# Pyr0-Piezo-FFC-Direct-Creality-X-Board_2.net
KiCad netlist of a schematic drawn in EAGLE
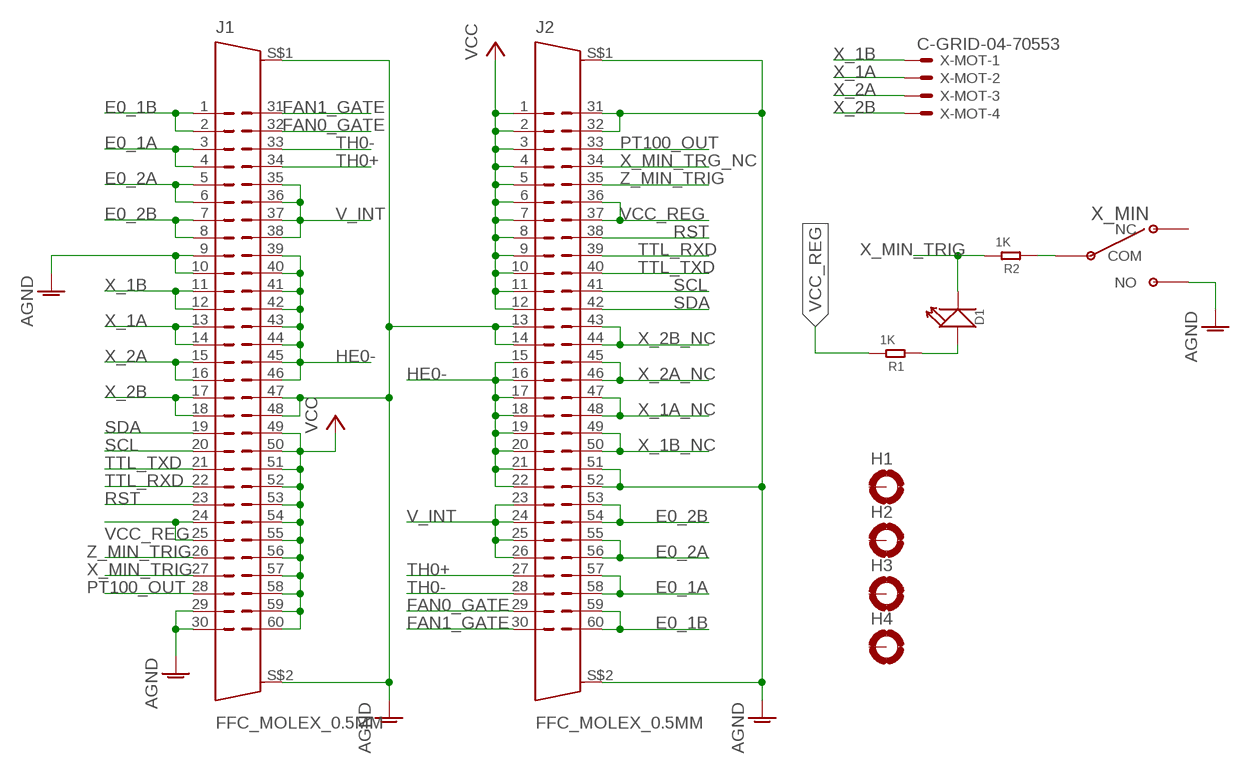
[diagram p0: schematic, sheet 1]

(export (version "E")
  (design (tool "Eeschema 10.0.6"))
  (components
    (comp (ref "D1")
      (value "SEEED-LED_SMD-LED-CLEAR-BLUE(0603)LED_0603")
      (footprint "eagle-import:SEEED-LED_LED-0603")
      (libsource (lib "eagle-import") (part "SEEED-LED_SMD-LED-CLEAR-BLUE(0603)LED_0603"))
    )
    (comp (ref "H1")
      (value "HOLES_MOUNT-PAD-ROUND3.2")
      (footprint "eagle-import:HOLES_3,2-PAD")
      (libsource (lib "eagle-import") (part "HOLES_MOUNT-PAD-ROUND3.2"))
    )
    (comp (ref "H2")
      (value "HOLES_MOUNT-PAD-ROUND3.2")
      (footprint "eagle-import:HOLES_3,2-PAD")
      (libsource (lib "eagle-import") (part "HOLES_MOUNT-PAD-ROUND3.2"))
    )
    (comp (ref "H3")
      (value "HOLES_MOUNT-PAD-ROUND3.2")
      (footprint "eagle-import:HOLES_3,2-PAD")
      (libsource (lib "eagle-import") (part "HOLES_MOUNT-PAD-ROUND3.2"))
    )
    (comp (ref "H4")
      (value "HOLES_MOUNT-PAD-ROUND3.2")
      (footprint "eagle-import:HOLES_3,2-PAD")
      (libsource (lib "eagle-import") (part "HOLES_MOUNT-PAD-ROUND3.2"))
    )
    (comp (ref "J1")
      (value "FFC_MOLEX_0.5MM")
      (footprint "eagle-import:FFC-60P_0.5_MOLEX_505110-6091")
      (libsource (lib "eagle-import") (part "FFC_MOLEX_0.5MM"))
    )
    (comp (ref "J2")
      (value "FFC_MOLEX_0.5MM")
      (footprint "eagle-import:FFC-60P_0.5_MOLEX_505110-6091")
      (libsource (lib "eagle-import") (part "FFC_MOLEX_0.5MM"))
    )
    (comp (ref "R1")
      (value "1K")
      (footprint "eagle-import:R0805")
      (fields (field (name "MPN") "RC0805JR-072KL"))
      (libsource (lib "eagle-import") (part "SMD-RES-2K-5%-1/8W(0805)"))
    )
    (comp (ref "R2")
      (value "1K")
      (footprint "eagle-import:R0805")
      (fields (field (name "MPN") "RC0805JR-072KL"))
      (libsource (lib "eagle-import") (part "SMD-RES-2K-5%-1/8W(0805)"))
    )
    (comp (ref "X-MOT")
      (value "C-GRID-04-70553")
      (footprint "eagle-import:70553-04")
      (fields (field (name "MF") "MOLEX"))
      (libsource (lib "eagle-import") (part "C-GRID-04-70553"))
    )
    (comp (ref "X_MIN")
      (value "LIMIT_SWITCHMICRO_SPDT_5.08")
      (footprint "eagle-import:MICROSWITCH_5.08")
      (libsource (lib "eagle-import") (part "LIMIT_SWITCHMICRO_SPDT_5.08"))
    )
  )
  (nets
    (net (code "1") (name "/E0_1A") (class "Default")
      (node (ref "J1") (pin "3") (pinfunction "5_3") (pintype "passive"))
      (node (ref "J1") (pin "4") (pinfunction "6_4") (pintype "passive"))
      (node (ref "J2") (pin "57") (pinfunction "63_57") (pintype "passive"))
      (node (ref "J2") (pin "58") (pinfunction "64_58") (pintype "passive"))
    )
    (net (code "2") (name "/E0_1B") (class "Default")
      (node (ref "J1") (pin "1") (pinfunction "3_1") (pintype "passive"))
      (node (ref "J1") (pin "2") (pinfunction "4_2") (pintype "passive"))
      (node (ref "J2") (pin "59") (pinfunction "65_59") (pintype "passive"))
      (node (ref "J2") (pin "60") (pinfunction "66_60") (pintype "passive"))
    )
    (net (code "3") (name "/E0_2A") (class "Default")
      (node (ref "J1") (pin "5") (pinfunction "7_5") (pintype "passive"))
      (node (ref "J1") (pin "6") (pinfunction "8_6") (pintype "passive"))
      (node (ref "J2") (pin "55") (pinfunction "61_55") (pintype "passive"))
      (node (ref "J2") (pin "56") (pinfunction "62_56") (pintype "passive"))
    )
    (net (code "4") (name "/E0_2B") (class "Default")
      (node (ref "J1") (pin "7") (pinfunction "9_7") (pintype "passive"))
      (node (ref "J1") (pin "8") (pinfunction "10_8") (pintype "passive"))
      (node (ref "J2") (pin "53") (pinfunction "59_53") (pintype "passive"))
      (node (ref "J2") (pin "54") (pinfunction "60_54") (pintype "passive"))
    )
    (net (code "5") (name "/FAN0_GATE") (class "Default")
      (node (ref "J1") (pin "32") (pinfunction "38_32") (pintype "passive"))
      (node (ref "J2") (pin "29") (pinfunction "31_29") (pintype "passive"))
    )
    (net (code "6") (name "/FAN1_GATE") (class "Default")
      (node (ref "J1") (pin "31") (pinfunction "37_31") (pintype "passive"))
      (node (ref "J2") (pin "30") (pinfunction "32_30") (pintype "passive"))
    )
    (net (code "7") (name "/HE0-") (class "Default")
      (node (ref "J1") (pin "39") (pinfunction "45_39") (pintype "passive"))
      (node (ref "J1") (pin "40") (pinfunction "46_40") (pintype "passive"))
      (node (ref "J1") (pin "41") (pinfunction "47_41") (pintype "passive"))
      (node (ref "J1") (pin "42") (pinfunction "48_42") (pintype "passive"))
      (node (ref "J1") (pin "43") (pinfunction "49_43") (pintype "passive"))
      (node (ref "J1") (pin "44") (pinfunction "50_44") (pintype "passive"))
      (node (ref "J1") (pin "45") (pinfunction "51_45") (pintype "passive"))
      (node (ref "J1") (pin "46") (pinfunction "52_46") (pintype "passive"))
      (node (ref "J2") (pin "15") (pinfunction "17_15") (pintype "passive"))
      (node (ref "J2") (pin "16") (pinfunction "18_16") (pintype "passive"))
      (node (ref "J2") (pin "17") (pinfunction "19_17") (pintype "passive"))
      (node (ref "J2") (pin "18") (pinfunction "20_18") (pintype "passive"))
      (node (ref "J2") (pin "19") (pinfunction "21_19") (pintype "passive"))
      (node (ref "J2") (pin "20") (pinfunction "22_20") (pintype "passive"))
      (node (ref "J2") (pin "21") (pinfunction "23_21") (pintype "passive"))
      (node (ref "J2") (pin "22") (pinfunction "24_22") (pintype "passive"))
    )
    (net (code "8") (name "/PT100_OUT") (class "Default")
      (node (ref "J1") (pin "28") (pinfunction "30_28") (pintype "passive"))
      (node (ref "J2") (pin "33") (pinfunction "39_33") (pintype "passive"))
    )
    (net (code "9") (name "/RST") (class "Default")
      (node (ref "J1") (pin "23") (pinfunction "25_23") (pintype "passive"))
      (node (ref "J2") (pin "38") (pinfunction "44_38") (pintype "passive"))
    )
    (net (code "10") (name "/SCL") (class "Default")
      (node (ref "J1") (pin "20") (pinfunction "22_20") (pintype "passive"))
      (node (ref "J2") (pin "41") (pinfunction "47_41") (pintype "passive"))
    )
    (net (code "11") (name "/SDA") (class "Default")
      (node (ref "J1") (pin "19") (pinfunction "21_19") (pintype "passive"))
      (node (ref "J2") (pin "42") (pinfunction "48_42") (pintype "passive"))
    )
    (net (code "12") (name "/TH0+") (class "Default")
      (node (ref "J1") (pin "34") (pinfunction "40_34") (pintype "passive"))
      (node (ref "J2") (pin "27") (pinfunction "29_27") (pintype "passive"))
    )
    (net (code "13") (name "/TH0-") (class "Default")
      (node (ref "J1") (pin "33") (pinfunction "39_33") (pintype "passive"))
      (node (ref "J2") (pin "28") (pinfunction "30_28") (pintype "passive"))
    )
    (net (code "14") (name "/TTL_RXD") (class "Default")
      (node (ref "J1") (pin "22") (pinfunction "24_22") (pintype "passive"))
      (node (ref "J2") (pin "39") (pinfunction "45_39") (pintype "passive"))
    )
    (net (code "15") (name "/TTL_TXD") (class "Default")
      (node (ref "J1") (pin "21") (pinfunction "23_21") (pintype "passive"))
      (node (ref "J2") (pin "40") (pinfunction "46_40") (pintype "passive"))
    )
    (net (code "16") (name "/V_INT") (class "Default")
      (node (ref "J1") (pin "35") (pinfunction "41_35") (pintype "passive"))
      (node (ref "J1") (pin "36") (pinfunction "42_36") (pintype "passive"))
      (node (ref "J1") (pin "37") (pinfunction "43_37") (pintype "passive"))
      (node (ref "J1") (pin "38") (pinfunction "44_38") (pintype "passive"))
      (node (ref "J2") (pin "23") (pinfunction "25_23") (pintype "passive"))
      (node (ref "J2") (pin "24") (pinfunction "26_24") (pintype "passive"))
      (node (ref "J2") (pin "25") (pinfunction "27_25") (pintype "passive"))
      (node (ref "J2") (pin "26") (pinfunction "28_26") (pintype "passive"))
    )
    (net (code "17") (name "/X_1A") (class "Default")
      (node (ref "J1") (pin "13") (pinfunction "15_13") (pintype "passive"))
      (node (ref "J1") (pin "14") (pinfunction "16_14") (pintype "passive"))
      (node (ref "X-MOT") (pin "2") (pinfunction "S_2") (pintype "passive"))
    )
    (net (code "18") (name "/X_1A_NC") (class "Default")
      (node (ref "J2") (pin "47") (pinfunction "53_47") (pintype "passive"))
      (node (ref "J2") (pin "48") (pinfunction "54_48") (pintype "passive"))
    )
    (net (code "19") (name "/X_1B") (class "Default")
      (node (ref "J1") (pin "11") (pinfunction "13_11") (pintype "passive"))
      (node (ref "J1") (pin "12") (pinfunction "14_12") (pintype "passive"))
      (node (ref "X-MOT") (pin "1") (pinfunction "S_1") (pintype "passive"))
    )
    (net (code "20") (name "/X_1B_NC") (class "Default")
      (node (ref "J2") (pin "49") (pinfunction "55_49") (pintype "passive"))
      (node (ref "J2") (pin "50") (pinfunction "56_50") (pintype "passive"))
    )
    (net (code "21") (name "/X_2A") (class "Default")
      (node (ref "J1") (pin "15") (pinfunction "17_15") (pintype "passive"))
      (node (ref "J1") (pin "16") (pinfunction "18_16") (pintype "passive"))
      (node (ref "X-MOT") (pin "3") (pinfunction "S_3") (pintype "passive"))
    )
    (net (code "22") (name "/X_2A_NC") (class "Default")
      (node (ref "J2") (pin "45") (pinfunction "51_45") (pintype "passive"))
      (node (ref "J2") (pin "46") (pinfunction "52_46") (pintype "passive"))
    )
    (net (code "23") (name "/X_2B") (class "Default")
      (node (ref "J1") (pin "17") (pinfunction "19_17") (pintype "passive"))
      (node (ref "J1") (pin "18") (pinfunction "20_18") (pintype "passive"))
      (node (ref "X-MOT") (pin "4") (pinfunction "S_4") (pintype "passive"))
    )
    (net (code "24") (name "/X_2B_NC") (class "Default")
      (node (ref "J2") (pin "43") (pinfunction "49_43") (pintype "passive"))
      (node (ref "J2") (pin "44") (pinfunction "50_44") (pintype "passive"))
    )
    (net (code "25") (name "/X_MIN_TRG_NC") (class "Default")
      (node (ref "J2") (pin "34") (pinfunction "40_34") (pintype "passive"))
    )
    (net (code "26") (name "/X_MIN_TRIG") (class "Default")
      (node (ref "D1") (pin "-") (pinfunction "-_-") (pintype "passive"))
      (node (ref "J1") (pin "27") (pinfunction "29_27") (pintype "passive"))
      (node (ref "R2") (pin "2") (pinfunction "2_2") (pintype "passive"))
    )
    (net (code "27") (name "/Z_MIN_TRIG") (class "Default")
      (node (ref "J1") (pin "26") (pinfunction "28_26") (pintype "passive"))
      (node (ref "J2") (pin "35") (pinfunction "41_35") (pintype "passive"))
    )
    (net (code "28") (name "AGND") (class "Default")
      (node (ref "J1") (pin "10") (pinfunction "12_10") (pintype "passive"))
      (node (ref "J1") (pin "29") (pinfunction "31_29") (pintype "passive"))
      (node (ref "J1") (pin "30") (pinfunction "32_30") (pintype "passive"))
      (node (ref "J1") (pin "47") (pinfunction "53_47") (pintype "passive"))
      (node (ref "J1") (pin "48") (pinfunction "54_48") (pintype "passive"))
      (node (ref "J1") (pin "9") (pinfunction "11_9") (pintype "passive"))
      (node (ref "J1") (pin "S$1") (pinfunction "S_S$1") (pintype "passive"))
      (node (ref "J1") (pin "S$2") (pinfunction "S_S$2") (pintype "passive"))
      (node (ref "J2") (pin "13") (pinfunction "15_13") (pintype "passive"))
      (node (ref "J2") (pin "14") (pinfunction "16_14") (pintype "passive"))
      (node (ref "J2") (pin "31") (pinfunction "37_31") (pintype "passive"))
      (node (ref "J2") (pin "32") (pinfunction "38_32") (pintype "passive"))
      (node (ref "J2") (pin "51") (pinfunction "57_51") (pintype "passive"))
      (node (ref "J2") (pin "52") (pinfunction "58_52") (pintype "passive"))
      (node (ref "J2") (pin "S$1") (pinfunction "S_S$1") (pintype "passive"))
      (node (ref "J2") (pin "S$2") (pinfunction "S_S$2") (pintype "passive"))
      (node (ref "X_MIN") (pin "P$2") (pinfunction "NO_P$2") (pintype "bidirectional"))
    )
    (net (code "29") (name "Net-(D1-Pad+)") (class "Default")
      (node (ref "D1") (pin "+") (pinfunction "+_+") (pintype "passive"))
      (node (ref "R1") (pin "1") (pinfunction "1_1") (pintype "passive"))
    )
    (net (code "30") (name "Net-(X_MIN-COM)") (class "Default")
      (node (ref "R2") (pin "1") (pinfunction "1_1") (pintype "passive"))
      (node (ref "X_MIN") (pin "P$1") (pinfunction "COM_P$1") (pintype "bidirectional"))
    )
    (net (code "31") (name "VCC") (class "Default")
      (node (ref "J1") (pin "49") (pinfunction "55_49") (pintype "passive"))
      (node (ref "J1") (pin "50") (pinfunction "56_50") (pintype "passive"))
      (node (ref "J1") (pin "51") (pinfunction "57_51") (pintype "passive"))
      (node (ref "J1") (pin "52") (pinfunction "58_52") (pintype "passive"))
      (node (ref "J1") (pin "53") (pinfunction "59_53") (pintype "passive"))
      (node (ref "J1") (pin "54") (pinfunction "60_54") (pintype "passive"))
      (node (ref "J1") (pin "55") (pinfunction "61_55") (pintype "passive"))
      (node (ref "J1") (pin "56") (pinfunction "62_56") (pintype "passive"))
      (node (ref "J1") (pin "57") (pinfunction "63_57") (pintype "passive"))
      (node (ref "J1") (pin "58") (pinfunction "64_58") (pintype "passive"))
      (node (ref "J1") (pin "59") (pinfunction "65_59") (pintype "passive"))
      (node (ref "J1") (pin "60") (pinfunction "66_60") (pintype "passive"))
      (node (ref "J2") (pin "1") (pinfunction "3_1") (pintype "passive"))
      (node (ref "J2") (pin "10") (pinfunction "12_10") (pintype "passive"))
      (node (ref "J2") (pin "11") (pinfunction "13_11") (pintype "passive"))
      (node (ref "J2") (pin "12") (pinfunction "14_12") (pintype "passive"))
      (node (ref "J2") (pin "2") (pinfunction "4_2") (pintype "passive"))
      (node (ref "J2") (pin "3") (pinfunction "5_3") (pintype "passive"))
      (node (ref "J2") (pin "4") (pinfunction "6_4") (pintype "passive"))
      (node (ref "J2") (pin "5") (pinfunction "7_5") (pintype "passive"))
      (node (ref "J2") (pin "6") (pinfunction "8_6") (pintype "passive"))
      (node (ref "J2") (pin "7") (pinfunction "9_7") (pintype "passive"))
      (node (ref "J2") (pin "8") (pinfunction "10_8") (pintype "passive"))
      (node (ref "J2") (pin "9") (pinfunction "11_9") (pintype "passive"))
    )
    (net (code "32") (name "VCC_REG") (class "Default")
      (node (ref "J1") (pin "24") (pinfunction "26_24") (pintype "passive"))
      (node (ref "J1") (pin "25") (pinfunction "27_25") (pintype "passive"))
      (node (ref "J2") (pin "36") (pinfunction "42_36") (pintype "passive"))
      (node (ref "J2") (pin "37") (pinfunction "43_37") (pintype "passive"))
      (node (ref "R1") (pin "2") (pinfunction "2_2") (pintype "passive"))
    )
    (net (code "33") (name "unconnected-(H1-MOUNT-PadB3,2)") (class "Default")
      (node (ref "H1") (pin "B3,2") (pinfunction "MOUNT_B3,2") (pintype "passive"))
    )
    (net (code "34") (name "unconnected-(H2-MOUNT-PadB3,2)") (class "Default")
      (node (ref "H2") (pin "B3,2") (pinfunction "MOUNT_B3,2") (pintype "passive"))
    )
    (net (code "35") (name "unconnected-(H3-MOUNT-PadB3,2)") (class "Default")
      (node (ref "H3") (pin "B3,2") (pinfunction "MOUNT_B3,2") (pintype "passive"))
    )
    (net (code "36") (name "unconnected-(H4-MOUNT-PadB3,2)") (class "Default")
      (node (ref "H4") (pin "B3,2") (pinfunction "MOUNT_B3,2") (pintype "passive"))
    )
    (net (code "37") (name "unconnected-(X_MIN-NC-PadP$3)") (class "Default")
      (node (ref "X_MIN") (pin "P$3") (pinfunction "NC_P$3") (pintype "bidirectional"))
    )
  )
)
